# DI_DO.net
KiCad netlist of a schematic drawn in Altium Designer
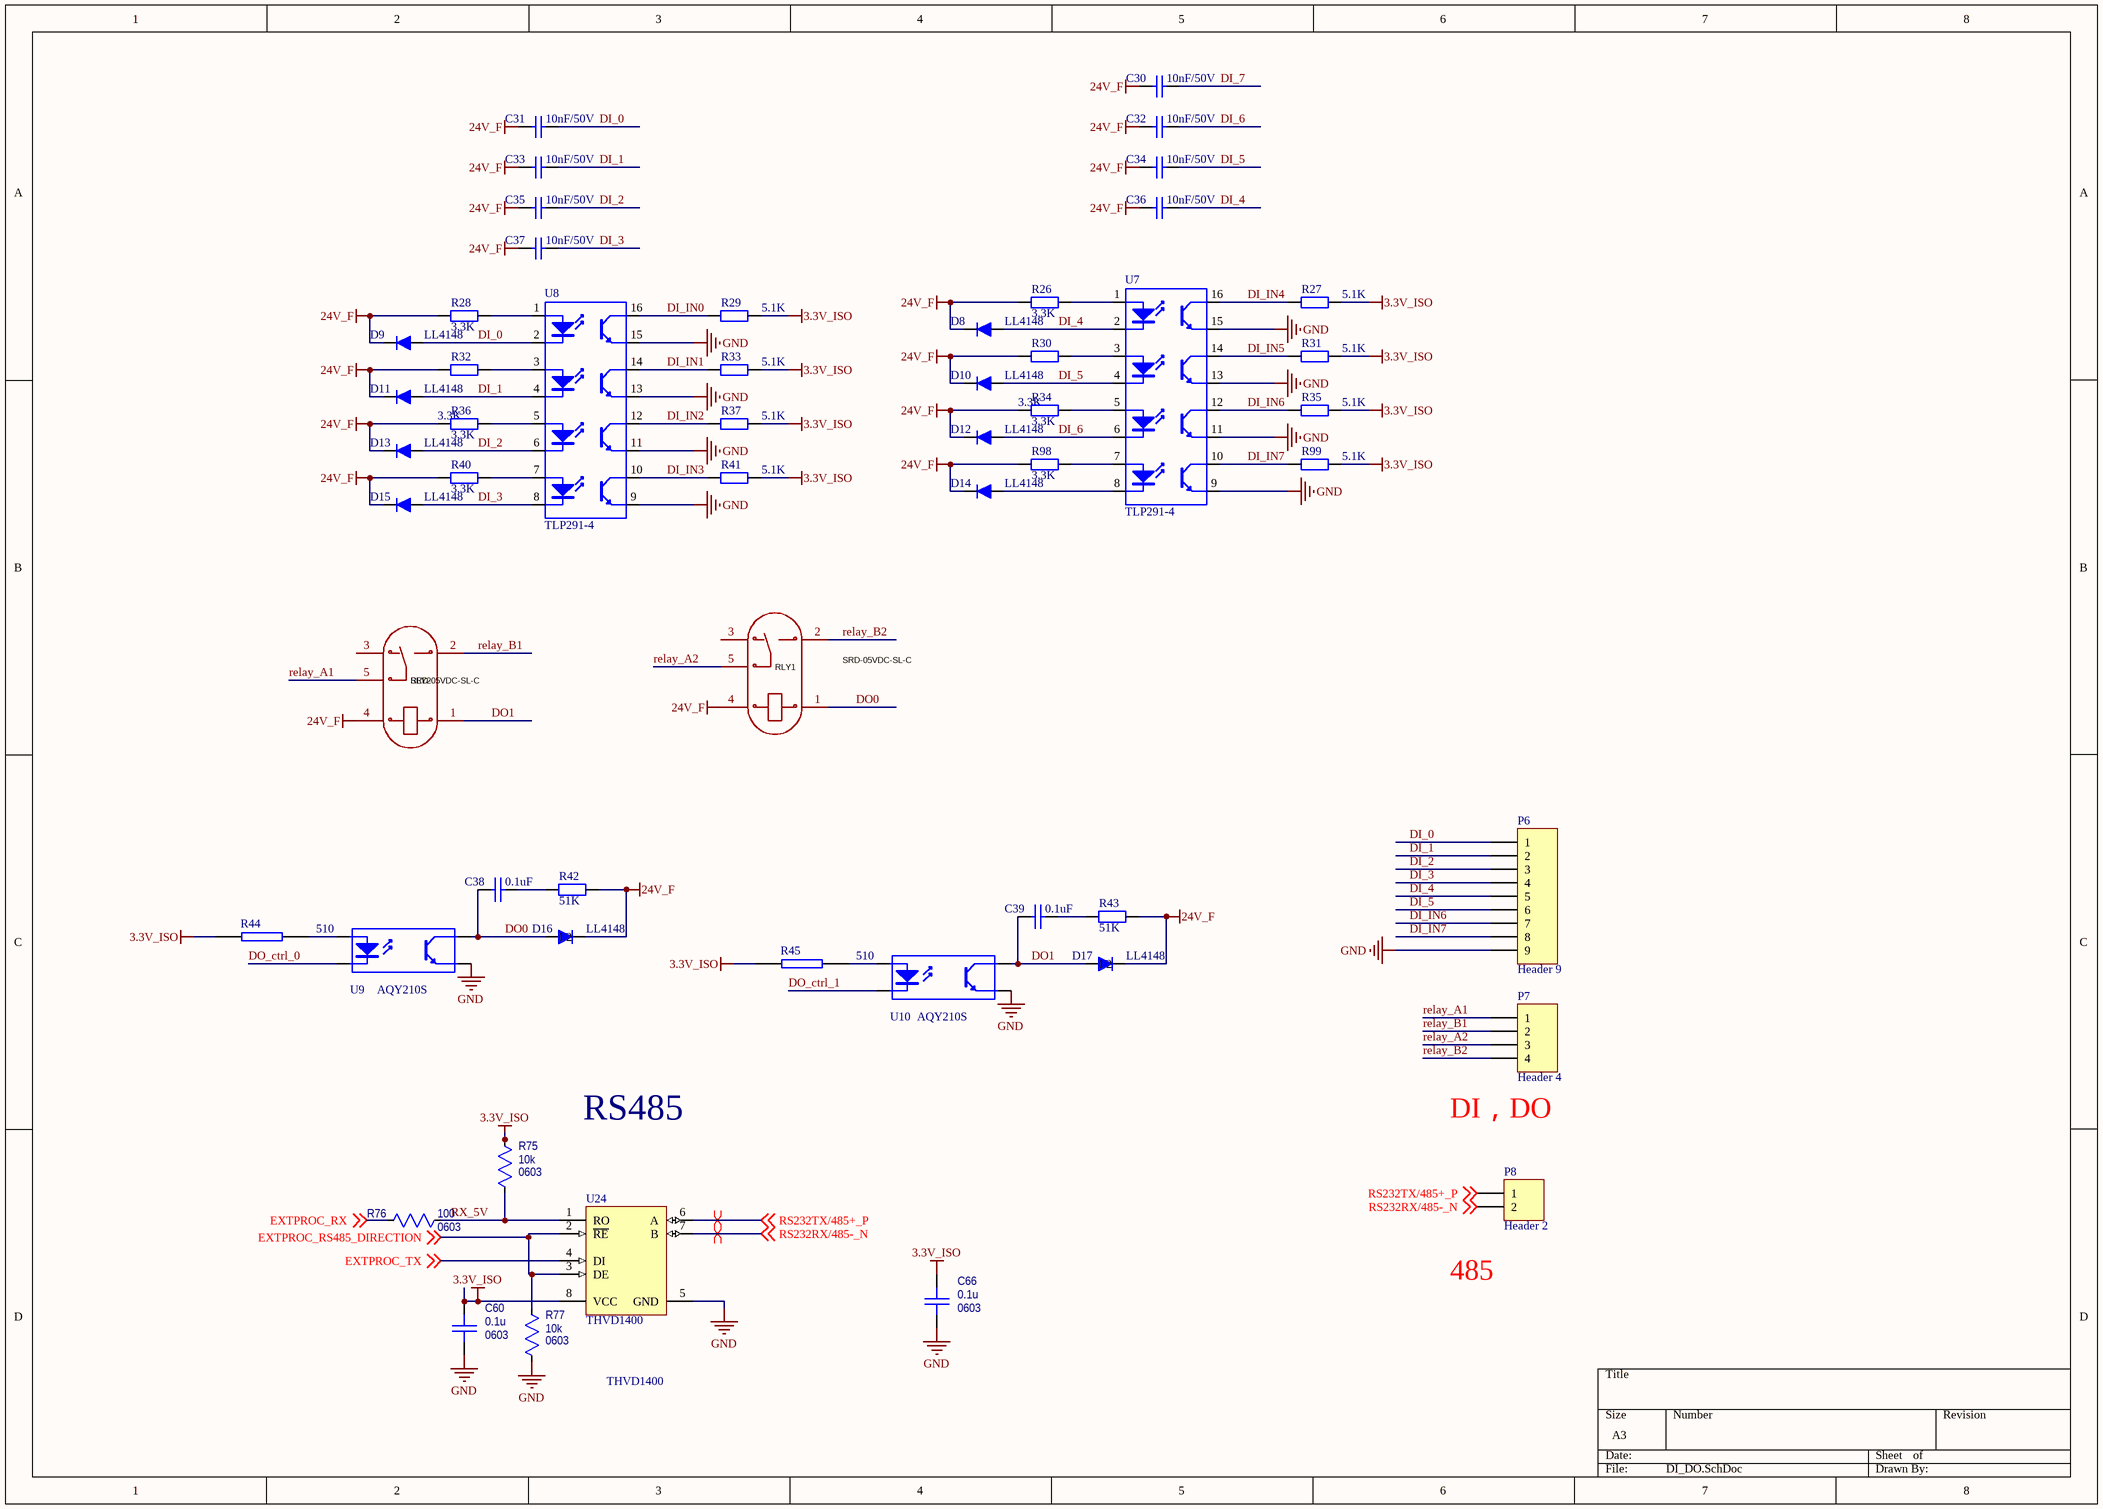
[diagram p0: DI_DO.SchDoc]

(export (version "E")
  (design (tool "Eeschema 10.0.6"))
  (components
    (comp (ref "C30")
      (value "10nF/50V")
      (footprint "0603C")
      (description "Capacitor")
      (fields (field (name "PUBLISHER") "Altium Limited"))
      (libsource (lib "Miscellaneous Devices") (part "Cap"))
    )
    (comp (ref "C31")
      (value "10nF/50V")
      (footprint "0603C")
      (description "Capacitor")
      (fields (field (name "PUBLISHER") "Altium Limited"))
      (libsource (lib "Miscellaneous Devices") (part "Cap"))
    )
    (comp (ref "C32")
      (value "10nF/50V")
      (footprint "0603C")
      (description "Capacitor")
      (fields (field (name "PUBLISHER") "Altium Limited"))
      (libsource (lib "Miscellaneous Devices") (part "Cap"))
    )
    (comp (ref "C33")
      (value "10nF/50V")
      (footprint "0603C")
      (description "Capacitor")
      (fields (field (name "PUBLISHER") "Altium Limited"))
      (libsource (lib "Miscellaneous Devices") (part "Cap"))
    )
    (comp (ref "C34")
      (value "10nF/50V")
      (footprint "0603C")
      (description "Capacitor")
      (fields (field (name "PUBLISHER") "Altium Limited"))
      (libsource (lib "Miscellaneous Devices") (part "Cap"))
    )
    (comp (ref "C35")
      (value "10nF/50V")
      (footprint "0603C")
      (description "Capacitor")
      (fields (field (name "PUBLISHER") "Altium Limited"))
      (libsource (lib "Miscellaneous Devices") (part "Cap"))
    )
    (comp (ref "C36")
      (value "10nF/50V")
      (footprint "0603C")
      (description "Capacitor")
      (fields (field (name "PUBLISHER") "Altium Limited"))
      (libsource (lib "Miscellaneous Devices") (part "Cap"))
    )
    (comp (ref "C37")
      (value "10nF/50V")
      (footprint "0603C")
      (description "Capacitor")
      (fields (field (name "PUBLISHER") "Altium Limited"))
      (libsource (lib "Miscellaneous Devices") (part "Cap"))
    )
    (comp (ref "C38")
      (value "0.1uF")
      (footprint "0603C")
      (description "Capacitor")
      (libsource (lib "*") (part "CAP"))
    )
    (comp (ref "C39")
      (value "0.1uF")
      (footprint "0603C")
      (description "Capacitor")
      (libsource (lib "*") (part "CAP"))
    )
    (comp (ref "C60")
      (value "0.1u")
      (footprint "CAPC1608X092N_0603")
      (description "Capacitor, MLCC")
      (fields
        (field (name "PARTNUMBER") "C0603C104M5RACTU")
        (field (name "TOLERANCE") "[tol]")
        (field (name "PACKAGE") "0603")
      )
      (libsource (lib "Karl") (part "Capacitor_0603"))
    )
    (comp (ref "C66")
      (value "0.1u")
      (footprint "CAPC1608X092N_0603")
      (description "Capacitor, MLCC")
      (fields
        (field (name "PARTNUMBER") "C0603C104M5RACTU")
        (field (name "TOLERANCE") "[tol]")
        (field (name "PACKAGE") "0603")
      )
      (libsource (lib "Karl") (part "Capacitor_0603"))
    )
    (comp (ref "D8")
      (value "LL4148")
      (footprint "DO-213AB/LL34/MiniMELF")
      (description "VISHAY,LL4148,圆柱体MiniMELF100V/2A,ROHS")
      (libsource (lib "Device2018") (part "LL4148"))
    )
    (comp (ref "D9")
      (value "LL4148")
      (footprint "DO-213AB/LL34/MiniMELF")
      (description "VISHAY,LL4148,圆柱体MiniMELF100V/2A,ROHS")
      (libsource (lib "Device2018") (part "LL4148"))
    )
    (comp (ref "D10")
      (value "LL4148")
      (footprint "DO-213AB/LL34/MiniMELF")
      (description "VISHAY,LL4148,圆柱体MiniMELF100V/2A,ROHS")
      (libsource (lib "Device2018") (part "LL4148"))
    )
    (comp (ref "D11")
      (value "LL4148")
      (footprint "DO-213AB/LL34/MiniMELF")
      (description "VISHAY,LL4148,圆柱体MiniMELF100V/2A,ROHS")
      (libsource (lib "Device2018") (part "LL4148"))
    )
    (comp (ref "D12")
      (value "LL4148")
      (footprint "DO-213AB/LL34/MiniMELF")
      (description "VISHAY,LL4148,圆柱体MiniMELF100V/2A,ROHS")
      (libsource (lib "Device2018") (part "LL4148"))
    )
    (comp (ref "D13")
      (value "LL4148")
      (footprint "DO-213AB/LL34/MiniMELF")
      (description "VISHAY,LL4148,圆柱体MiniMELF100V/2A,ROHS")
      (libsource (lib "Device2018") (part "LL4148"))
    )
    (comp (ref "D14")
      (value "LL4148")
      (footprint "DO-213AB/LL34/MiniMELF")
      (description "VISHAY,LL4148,圆柱体MiniMELF100V/2A,ROHS")
      (libsource (lib "Device2018") (part "LL4148"))
    )
    (comp (ref "D15")
      (value "LL4148")
      (footprint "DO-213AB/LL34/MiniMELF")
      (description "VISHAY,LL4148,圆柱体MiniMELF100V/2A,ROHS")
      (libsource (lib "Device2018") (part "LL4148"))
    )
    (comp (ref "D16")
      (value "LL4148")
      (footprint "DO-213AB/LL34/MiniMELF")
      (description "VISHAY,LL4148,圆柱体MiniMELF100V/2A,ROHS")
      (libsource (lib "") (part "LL4148_1"))
    )
    (comp (ref "D17")
      (value "LL4148")
      (footprint "DO-213AB/LL34/MiniMELF")
      (description "VISHAY,LL4148,圆柱体MiniMELF100V/2A,ROHS")
      (libsource (lib "") (part "LL4148_1"))
    )
    (comp (ref "P6")
      (value "Header 9")
      (footprint "HDR1X9")
      (description "Header, 9-Pin")
      (fields (field (name "PUBLISHER") "Altium Limited"))
      (libsource (lib "Miscellaneous Connectors") (part "Header 9"))
    )
    (comp (ref "P7")
      (value "Header 4")
      (footprint "HDR1X4")
      (description "Header, 4-Pin")
      (fields (field (name "PUBLISHER") "Altium Limited"))
      (libsource (lib "Miscellaneous Connectors") (part "Header 4"))
    )
    (comp (ref "P8")
      (value "Header 2")
      (footprint "HDR1X2")
      (description "Header, 2-Pin")
      (fields (field (name "PUBLISHER") "Altium Limited"))
      (libsource (lib "Miscellaneous Connectors") (part "Header 2"))
    )
    (comp (ref "R26") (value "3.3K") (footprint "0603R") (libsource (lib "MQlibrary") (part "Res0805M")))
    (comp (ref "R27") (value "5.1K") (footprint "0603R") (libsource (lib "MQlibrary") (part "Res0805M")))
    (comp (ref "R28") (value "3.3K") (footprint "0603R") (libsource (lib "MQlibrary") (part "Res0805M")))
    (comp (ref "R29") (value "5.1K") (footprint "0603R") (libsource (lib "MQlibrary") (part "Res0805M")))
    (comp (ref "R30") (value "3.3K") (footprint "0603R") (libsource (lib "MQlibrary") (part "Res0805M")))
    (comp (ref "R31") (value "5.1K") (footprint "0603R") (libsource (lib "MQlibrary") (part "Res0805M")))
    (comp (ref "R32") (value "3.3K") (footprint "0603R") (libsource (lib "MQlibrary") (part "Res0805M")))
    (comp (ref "R33") (value "5.1K") (footprint "0603R") (libsource (lib "MQlibrary") (part "Res0805M")))
    (comp (ref "R34") (value "3.3K") (footprint "0603R") (libsource (lib "MQlibrary") (part "Res0805M")))
    (comp (ref "R35") (value "5.1K") (footprint "0603R") (libsource (lib "MQlibrary") (part "Res0805M")))
    (comp (ref "R36") (value "3.3K") (footprint "0603R") (libsource (lib "MQlibrary") (part "Res0805M")))
    (comp (ref "R37") (value "5.1K") (footprint "0603R") (libsource (lib "MQlibrary") (part "Res0805M")))
    (comp (ref "R40") (value "3.3K") (footprint "0603R") (libsource (lib "MQlibrary") (part "Res0805M")))
    (comp (ref "R41") (value "5.1K") (footprint "0603R") (libsource (lib "MQlibrary") (part "Res0805M")))
    (comp (ref "R42") (value "51K") (footprint "0603R") (libsource (lib "") (part "Res0805M_1")))
    (comp (ref "R43") (value "51K") (footprint "0603R") (libsource (lib "") (part "Res0805M_1")))
    (comp (ref "R44") (value "510") (footprint "0603R") (libsource (lib "*") (part "RES2")))
    (comp (ref "R45") (value "510") (footprint "0603R") (libsource (lib "*") (part "RES2")))
    (comp (ref "R75")
      (value "10k")
      (footprint "RESC1608X055N_0603")
      (description "Resistor, Standard")
      (fields
        (field (name "PARTNUMBER") "RC0603FR-0710KL")
        (field (name "TOLERANCE") "tol")
        (field (name "PACKAGE") "0603")
      )
      (libsource (lib "Karl") (part "Resistor_0603"))
    )
    (comp (ref "R76")
      (value "100")
      (footprint "RESC1608X055N_0603")
      (description "Resistor, Standard")
      (fields
        (field (name "PARTNUMBER") "RC0603FR-07100RL")
        (field (name "TOLERANCE") "tol")
        (field (name "PACKAGE") "0603")
      )
      (libsource (lib "Karl") (part "Resistor_0603"))
    )
    (comp (ref "R77")
      (value "10k")
      (footprint "RESC1608X055N_0603")
      (description "Resistor, Standard")
      (fields
        (field (name "PARTNUMBER") "RC0603FR-0710KL")
        (field (name "TOLERANCE") "tol")
        (field (name "PACKAGE") "0603")
      )
      (libsource (lib "Karl") (part "Resistor_0603"))
    )
    (comp (ref "R98") (value "3.3K") (footprint "0603R") (libsource (lib "MQlibrary") (part "Res0805M")))
    (comp (ref "R99") (value "5.1K") (footprint "0603R") (libsource (lib "MQlibrary") (part "Res0805M")))
    (comp (ref "RLY1")
      (value "SRD-05VDC-SL-C")
      (footprint "RELAY-TH_SRD-XXVDC-XL-C")
      (fields (field (name "MANUFACTURER") "松乐"))
      (libsource (lib "altium-import") (part "root_0_SRD-05VDC-SL-C_"))
    )
    (comp (ref "RLY2")
      (value "SRD-05VDC-SL-C")
      (footprint "RELAY-TH_SRD-XXVDC-XL-C")
      (fields (field (name "MANUFACTURER") "松乐"))
      (libsource (lib "altium-import") (part "root_0_SRD-05VDC-SL-C_"))
    )
    (comp (ref "U7") (value "TLP291-4") (footprint "SOP16-T") (libsource (lib "DI16") (part "TLP281-4")))
    (comp (ref "U8") (value "TLP291-4") (footprint "SOP16-T") (libsource (lib "DI16") (part "TLP281-4")))
    (comp (ref "U9")
      (value "AQY210S")
      (footprint "sop4")
      (description "4-Pin Phototransistor Optocoupler")
      (fields (field (name "PUBLISHER") "Altium Limited"))
      (libsource (lib "Miscellaneous Devices") (part "Optoisolator1"))
    )
    (comp (ref "U10")
      (value "AQY210S")
      (footprint "sop4")
      (description "4-Pin Phototransistor Optocoupler")
      (fields (field (name "PUBLISHER") "Altium Limited"))
      (libsource (lib "Miscellaneous Devices") (part "Optoisolator1"))
    )
    (comp (ref "U24")
      (value "THVD1400")
      (footprint "MAXM-S8+4_M")
      (fields (field (name "PARTNUMBER") "MAX33071EASA+"))
      (libsource (lib "Bogen") (part "MAX33071EASA+"))
    )
  )
  (nets
    (net (code "1") (name "/DI_0") (class "Default")
      (node (ref "C31") (pin "2") (pinfunction "2_2") (pintype "passive"))
      (node (ref "D9") (pin "1") (pinfunction "2_1") (pintype "passive"))
      (node (ref "P6") (pin "1") (pinfunction "1_1") (pintype "passive"))
      (node (ref "U8") (pin "2") (pinfunction "K_2") (pintype "passive"))
    )
    (net (code "2") (name "/DI_1") (class "Default")
      (node (ref "C33") (pin "2") (pinfunction "2_2") (pintype "passive"))
      (node (ref "D11") (pin "1") (pinfunction "2_1") (pintype "passive"))
      (node (ref "P6") (pin "2") (pinfunction "2_2") (pintype "passive"))
      (node (ref "U8") (pin "4") (pinfunction "K_4") (pintype "passive"))
    )
    (net (code "3") (name "/DI_2") (class "Default")
      (node (ref "C35") (pin "2") (pinfunction "2_2") (pintype "passive"))
      (node (ref "D13") (pin "1") (pinfunction "2_1") (pintype "passive"))
      (node (ref "P6") (pin "3") (pinfunction "3_3") (pintype "passive"))
      (node (ref "U8") (pin "6") (pinfunction "K_6") (pintype "passive"))
    )
    (net (code "4") (name "/DI_3") (class "Default")
      (node (ref "C37") (pin "2") (pinfunction "2_2") (pintype "passive"))
      (node (ref "D15") (pin "1") (pinfunction "2_1") (pintype "passive"))
      (node (ref "P6") (pin "4") (pinfunction "4_4") (pintype "passive"))
      (node (ref "U8") (pin "8") (pinfunction "K_8") (pintype "passive"))
    )
    (net (code "5") (name "/DI_4") (class "Default")
      (node (ref "C36") (pin "2") (pinfunction "2_2") (pintype "passive"))
      (node (ref "D8") (pin "1") (pinfunction "2_1") (pintype "passive"))
      (node (ref "P6") (pin "5") (pinfunction "5_5") (pintype "passive"))
      (node (ref "U7") (pin "2") (pinfunction "K_2") (pintype "passive"))
    )
    (net (code "6") (name "/DI_5") (class "Default")
      (node (ref "C34") (pin "2") (pinfunction "2_2") (pintype "passive"))
      (node (ref "D10") (pin "1") (pinfunction "2_1") (pintype "passive"))
      (node (ref "P6") (pin "6") (pinfunction "6_6") (pintype "passive"))
      (node (ref "U7") (pin "4") (pinfunction "K_4") (pintype "passive"))
    )
    (net (code "7") (name "/DI_6") (class "Default")
      (node (ref "C32") (pin "2") (pinfunction "2_2") (pintype "passive"))
      (node (ref "D12") (pin "1") (pinfunction "2_1") (pintype "passive"))
      (node (ref "U7") (pin "6") (pinfunction "K_6") (pintype "passive"))
    )
    (net (code "8") (name "/DI_7") (class "Default")
      (node (ref "C30") (pin "2") (pinfunction "2_2") (pintype "passive"))
    )
    (net (code "9") (name "/DI_IN0") (class "Default")
      (node (ref "R29") (pin "2") (pinfunction "2_2") (pintype "passive"))
      (node (ref "U8") (pin "16") (pinfunction "C_16") (pintype "passive"))
    )
    (net (code "10") (name "/DI_IN1") (class "Default")
      (node (ref "R33") (pin "2") (pinfunction "2_2") (pintype "passive"))
      (node (ref "U8") (pin "14") (pinfunction "C_14") (pintype "passive"))
    )
    (net (code "11") (name "/DI_IN2") (class "Default")
      (node (ref "R37") (pin "2") (pinfunction "2_2") (pintype "passive"))
      (node (ref "U8") (pin "12") (pinfunction "C_12") (pintype "passive"))
    )
    (net (code "12") (name "/DI_IN3") (class "Default")
      (node (ref "R41") (pin "2") (pinfunction "2_2") (pintype "passive"))
      (node (ref "U8") (pin "10") (pinfunction "C_10") (pintype "passive"))
    )
    (net (code "13") (name "/DI_IN4") (class "Default")
      (node (ref "R27") (pin "2") (pinfunction "2_2") (pintype "passive"))
      (node (ref "U7") (pin "16") (pinfunction "C_16") (pintype "passive"))
    )
    (net (code "14") (name "/DI_IN5") (class "Default")
      (node (ref "R31") (pin "2") (pinfunction "2_2") (pintype "passive"))
      (node (ref "U7") (pin "14") (pinfunction "C_14") (pintype "passive"))
    )
    (net (code "15") (name "/DI_IN6") (class "Default")
      (node (ref "P6") (pin "7") (pinfunction "7_7") (pintype "passive"))
      (node (ref "R35") (pin "2") (pinfunction "2_2") (pintype "passive"))
      (node (ref "U7") (pin "12") (pinfunction "C_12") (pintype "passive"))
    )
    (net (code "16") (name "/DI_IN7") (class "Default")
      (node (ref "P6") (pin "8") (pinfunction "8_8") (pintype "passive"))
      (node (ref "R99") (pin "2") (pinfunction "2_2") (pintype "passive"))
      (node (ref "U7") (pin "10") (pinfunction "C_10") (pintype "passive"))
    )
    (net (code "17") (name "/DO0") (class "Default")
      (node (ref "C38") (pin "1") (pinfunction "1_1") (pintype "passive"))
      (node (ref "D16") (pin "1") (pinfunction "2_1") (pintype "passive"))
      (node (ref "RLY1") (pin "1") (pinfunction "1_1") (pintype "passive"))
      (node (ref "U9") (pin "4") (pinfunction "C_4") (pintype "passive"))
    )
    (net (code "18") (name "/DO1") (class "Default")
      (node (ref "C39") (pin "1") (pinfunction "1_1") (pintype "passive"))
      (node (ref "D17") (pin "1") (pinfunction "2_1") (pintype "passive"))
      (node (ref "RLY2") (pin "1") (pinfunction "1_1") (pintype "passive"))
      (node (ref "U10") (pin "4") (pinfunction "C_4") (pintype "passive"))
    )
    (net (code "19") (name "/DO_ctrl_0") (class "Default")
      (node (ref "U9") (pin "2") (pinfunction "K_2") (pintype "passive"))
    )
    (net (code "20") (name "/DO_ctrl_1") (class "Default")
      (node (ref "U10") (pin "2") (pinfunction "K_2") (pintype "passive"))
    )
    (net (code "21") (name "/RX_5V") (class "Default")
      (node (ref "R75") (pin "1") (pinfunction "1_1") (pintype "passive"))
      (node (ref "R76") (pin "1") (pinfunction "1_1") (pintype "passive"))
      (node (ref "U24") (pin "1") (pinfunction "RO_1") (pintype "tri_state"))
    )
    (net (code "22") (name "/relay_A1") (class "Default")
      (node (ref "P7") (pin "1") (pinfunction "1_1") (pintype "passive"))
      (node (ref "RLY2") (pin "5") (pinfunction "5_5") (pintype "passive"))
    )
    (net (code "23") (name "/relay_A2") (class "Default")
      (node (ref "P7") (pin "3") (pinfunction "3_3") (pintype "passive"))
      (node (ref "RLY1") (pin "5") (pinfunction "5_5") (pintype "passive"))
    )
    (net (code "24") (name "/relay_B1") (class "Default")
      (node (ref "P7") (pin "2") (pinfunction "2_2") (pintype "passive"))
      (node (ref "RLY2") (pin "2") (pinfunction "2_2") (pintype "passive"))
    )
    (net (code "25") (name "/relay_B2") (class "Default")
      (node (ref "P7") (pin "4") (pinfunction "4_4") (pintype "passive"))
      (node (ref "RLY1") (pin "2") (pinfunction "2_2") (pintype "passive"))
    )
    (net (code "26") (name "3.3V_ISO") (class "Default")
      (node (ref "C60") (pin "1") (pinfunction "1_1") (pintype "passive"))
      (node (ref "C66") (pin "1") (pinfunction "1_1") (pintype "passive"))
      (node (ref "R27") (pin "1") (pinfunction "1_1") (pintype "passive"))
      (node (ref "R29") (pin "1") (pinfunction "1_1") (pintype "passive"))
      (node (ref "R31") (pin "1") (pinfunction "1_1") (pintype "passive"))
      (node (ref "R33") (pin "1") (pinfunction "1_1") (pintype "passive"))
      (node (ref "R35") (pin "1") (pinfunction "1_1") (pintype "passive"))
      (node (ref "R37") (pin "1") (pinfunction "1_1") (pintype "passive"))
      (node (ref "R41") (pin "1") (pinfunction "1_1") (pintype "passive"))
      (node (ref "R44") (pin "2") (pinfunction "2_2") (pintype "passive"))
      (node (ref "R45") (pin "2") (pinfunction "2_2") (pintype "passive"))
      (node (ref "R75") (pin "2") (pinfunction "2_2") (pintype "passive"))
      (node (ref "R99") (pin "1") (pinfunction "1_1") (pintype "passive"))
      (node (ref "U24") (pin "8") (pinfunction "VCC_8") (pintype "power_in"))
    )
    (net (code "27") (name "24V_F") (class "Default")
      (node (ref "C30") (pin "1") (pinfunction "1_1") (pintype "passive"))
      (node (ref "C31") (pin "1") (pinfunction "1_1") (pintype "passive"))
      (node (ref "C32") (pin "1") (pinfunction "1_1") (pintype "passive"))
      (node (ref "C33") (pin "1") (pinfunction "1_1") (pintype "passive"))
      (node (ref "C34") (pin "1") (pinfunction "1_1") (pintype "passive"))
      (node (ref "C35") (pin "1") (pinfunction "1_1") (pintype "passive"))
      (node (ref "C36") (pin "1") (pinfunction "1_1") (pintype "passive"))
      (node (ref "C37") (pin "1") (pinfunction "1_1") (pintype "passive"))
      (node (ref "D10") (pin "2") (pinfunction "1_2") (pintype "passive"))
      (node (ref "D11") (pin "2") (pinfunction "1_2") (pintype "passive"))
      (node (ref "D12") (pin "2") (pinfunction "1_2") (pintype "passive"))
      (node (ref "D13") (pin "2") (pinfunction "1_2") (pintype "passive"))
      (node (ref "D14") (pin "2") (pinfunction "1_2") (pintype "passive"))
      (node (ref "D15") (pin "2") (pinfunction "1_2") (pintype "passive"))
      (node (ref "D16") (pin "2") (pinfunction "1_2") (pintype "passive"))
      (node (ref "D17") (pin "2") (pinfunction "1_2") (pintype "passive"))
      (node (ref "D8") (pin "2") (pinfunction "1_2") (pintype "passive"))
      (node (ref "D9") (pin "2") (pinfunction "1_2") (pintype "passive"))
      (node (ref "R26") (pin "2") (pinfunction "2_2") (pintype "passive"))
      (node (ref "R28") (pin "2") (pinfunction "2_2") (pintype "passive"))
      (node (ref "R30") (pin "2") (pinfunction "2_2") (pintype "passive"))
      (node (ref "R32") (pin "2") (pinfunction "2_2") (pintype "passive"))
      (node (ref "R34") (pin "2") (pinfunction "2_2") (pintype "passive"))
      (node (ref "R36") (pin "2") (pinfunction "2_2") (pintype "passive"))
      (node (ref "R40") (pin "2") (pinfunction "2_2") (pintype "passive"))
      (node (ref "R42") (pin "2") (pinfunction "2_2") (pintype "passive"))
      (node (ref "R43") (pin "2") (pinfunction "2_2") (pintype "passive"))
      (node (ref "R98") (pin "2") (pinfunction "2_2") (pintype "passive"))
      (node (ref "RLY1") (pin "4") (pinfunction "4_4") (pintype "passive"))
      (node (ref "RLY2") (pin "4") (pinfunction "4_4") (pintype "passive"))
    )
    (net (code "28") (name "EXTPROC_RS485_DIRECTION") (class "Default")
      (node (ref "R77") (pin "2") (pinfunction "2_2") (pintype "passive"))
      (node (ref "U24") (pin "2") (pinfunction "~{RE}_2") (pintype "input"))
      (node (ref "U24") (pin "3") (pinfunction "DE_3") (pintype "input"))
    )
    (net (code "29") (name "EXTPROC_RX") (class "Default")
      (node (ref "R76") (pin "2") (pinfunction "2_2") (pintype "passive"))
    )
    (net (code "30") (name "EXTPROC_TX") (class "Default")
      (node (ref "U24") (pin "4") (pinfunction "DI_4") (pintype "input"))
    )
    (net (code "31") (name "GND") (class "Default")
      (node (ref "C60") (pin "2") (pinfunction "2_2") (pintype "passive"))
      (node (ref "C66") (pin "2") (pinfunction "2_2") (pintype "passive"))
      (node (ref "P6") (pin "9") (pinfunction "9_9") (pintype "passive"))
      (node (ref "R77") (pin "1") (pinfunction "1_1") (pintype "passive"))
      (node (ref "U10") (pin "3") (pinfunction "E_3") (pintype "passive"))
      (node (ref "U24") (pin "5") (pinfunction "GND_5") (pintype "power_in"))
      (node (ref "U7") (pin "11") (pinfunction "E_11") (pintype "passive"))
      (node (ref "U7") (pin "13") (pinfunction "E_13") (pintype "passive"))
      (node (ref "U7") (pin "15") (pinfunction "E_15") (pintype "passive"))
      (node (ref "U7") (pin "9") (pinfunction "E_9") (pintype "passive"))
      (node (ref "U8") (pin "11") (pinfunction "E_11") (pintype "passive"))
      (node (ref "U8") (pin "13") (pinfunction "E_13") (pintype "passive"))
      (node (ref "U8") (pin "15") (pinfunction "E_15") (pintype "passive"))
      (node (ref "U8") (pin "9") (pinfunction "E_9") (pintype "passive"))
      (node (ref "U9") (pin "3") (pinfunction "E_3") (pintype "passive"))
    )
    (net (code "32") (name "Net-(C38-Pad2)") (class "Default")
      (node (ref "C38") (pin "2") (pinfunction "2_2") (pintype "passive"))
      (node (ref "R42") (pin "1") (pinfunction "1_1") (pintype "passive"))
    )
    (net (code "33") (name "Net-(C39-Pad2)") (class "Default")
      (node (ref "C39") (pin "2") (pinfunction "2_2") (pintype "passive"))
      (node (ref "R43") (pin "1") (pinfunction "1_1") (pintype "passive"))
    )
    (net (code "34") (name "Net-(D14-2)") (class "Default")
      (node (ref "D14") (pin "1") (pinfunction "2_1") (pintype "passive"))
      (node (ref "U7") (pin "8") (pinfunction "K_8") (pintype "passive"))
    )
    (net (code "35") (name "Net-(R26-Pad1)") (class "Default")
      (node (ref "R26") (pin "1") (pinfunction "1_1") (pintype "passive"))
      (node (ref "U7") (pin "1") (pinfunction "A_1") (pintype "passive"))
    )
    (net (code "36") (name "Net-(R28-Pad1)") (class "Default")
      (node (ref "R28") (pin "1") (pinfunction "1_1") (pintype "passive"))
      (node (ref "U8") (pin "1") (pinfunction "A_1") (pintype "passive"))
    )
    (net (code "37") (name "Net-(R30-Pad1)") (class "Default")
      (node (ref "R30") (pin "1") (pinfunction "1_1") (pintype "passive"))
      (node (ref "U7") (pin "3") (pinfunction "A_3") (pintype "passive"))
    )
    (net (code "38") (name "Net-(R32-Pad1)") (class "Default")
      (node (ref "R32") (pin "1") (pinfunction "1_1") (pintype "passive"))
      (node (ref "U8") (pin "3") (pinfunction "A_3") (pintype "passive"))
    )
    (net (code "39") (name "Net-(R34-Pad1)") (class "Default")
      (node (ref "R34") (pin "1") (pinfunction "1_1") (pintype "passive"))
      (node (ref "U7") (pin "5") (pinfunction "A_5") (pintype "passive"))
    )
    (net (code "40") (name "Net-(R36-Pad1)") (class "Default")
      (node (ref "R36") (pin "1") (pinfunction "1_1") (pintype "passive"))
      (node (ref "U8") (pin "5") (pinfunction "A_5") (pintype "passive"))
    )
    (net (code "41") (name "Net-(R40-Pad1)") (class "Default")
      (node (ref "R40") (pin "1") (pinfunction "1_1") (pintype "passive"))
      (node (ref "U8") (pin "7") (pinfunction "A_7") (pintype "passive"))
    )
    (net (code "42") (name "Net-(R98-Pad1)") (class "Default")
      (node (ref "R98") (pin "1") (pinfunction "1_1") (pintype "passive"))
      (node (ref "U7") (pin "7") (pinfunction "A_7") (pintype "passive"))
    )
    (net (code "43") (name "Net-(U9-A)") (class "Default")
      (node (ref "R44") (pin "1") (pinfunction "1_1") (pintype "passive"))
      (node (ref "U9") (pin "1") (pinfunction "A_1") (pintype "passive"))
    )
    (net (code "44") (name "Net-(U10-A)") (class "Default")
      (node (ref "R45") (pin "1") (pinfunction "1_1") (pintype "passive"))
      (node (ref "U10") (pin "1") (pinfunction "A_1") (pintype "passive"))
    )
    (net (code "45") (name "RS232RX{slash}485-_N") (class "Default")
      (node (ref "P8") (pin "2") (pinfunction "2_2") (pintype "passive"))
      (node (ref "U24") (pin "7") (pinfunction "B_7") (pintype "bidirectional"))
    )
    (net (code "46") (name "RS232TX{slash}485+_P") (class "Default")
      (node (ref "P8") (pin "1") (pinfunction "1_1") (pintype "passive"))
      (node (ref "U24") (pin "6") (pinfunction "A_6") (pintype "bidirectional"))
    )
    (net (code "47") (name "unconnected-(RLY1-Pad3)") (class "Default")
      (node (ref "RLY1") (pin "3") (pinfunction "3_3") (pintype "passive"))
    )
    (net (code "48") (name "unconnected-(RLY2-Pad3)") (class "Default")
      (node (ref "RLY2") (pin "3") (pinfunction "3_3") (pintype "passive"))
    )
  )
)
